# Geoffrey_s_Holiday_Ornament_Design.net
KiCad netlist of a schematic drawn in EAGLE
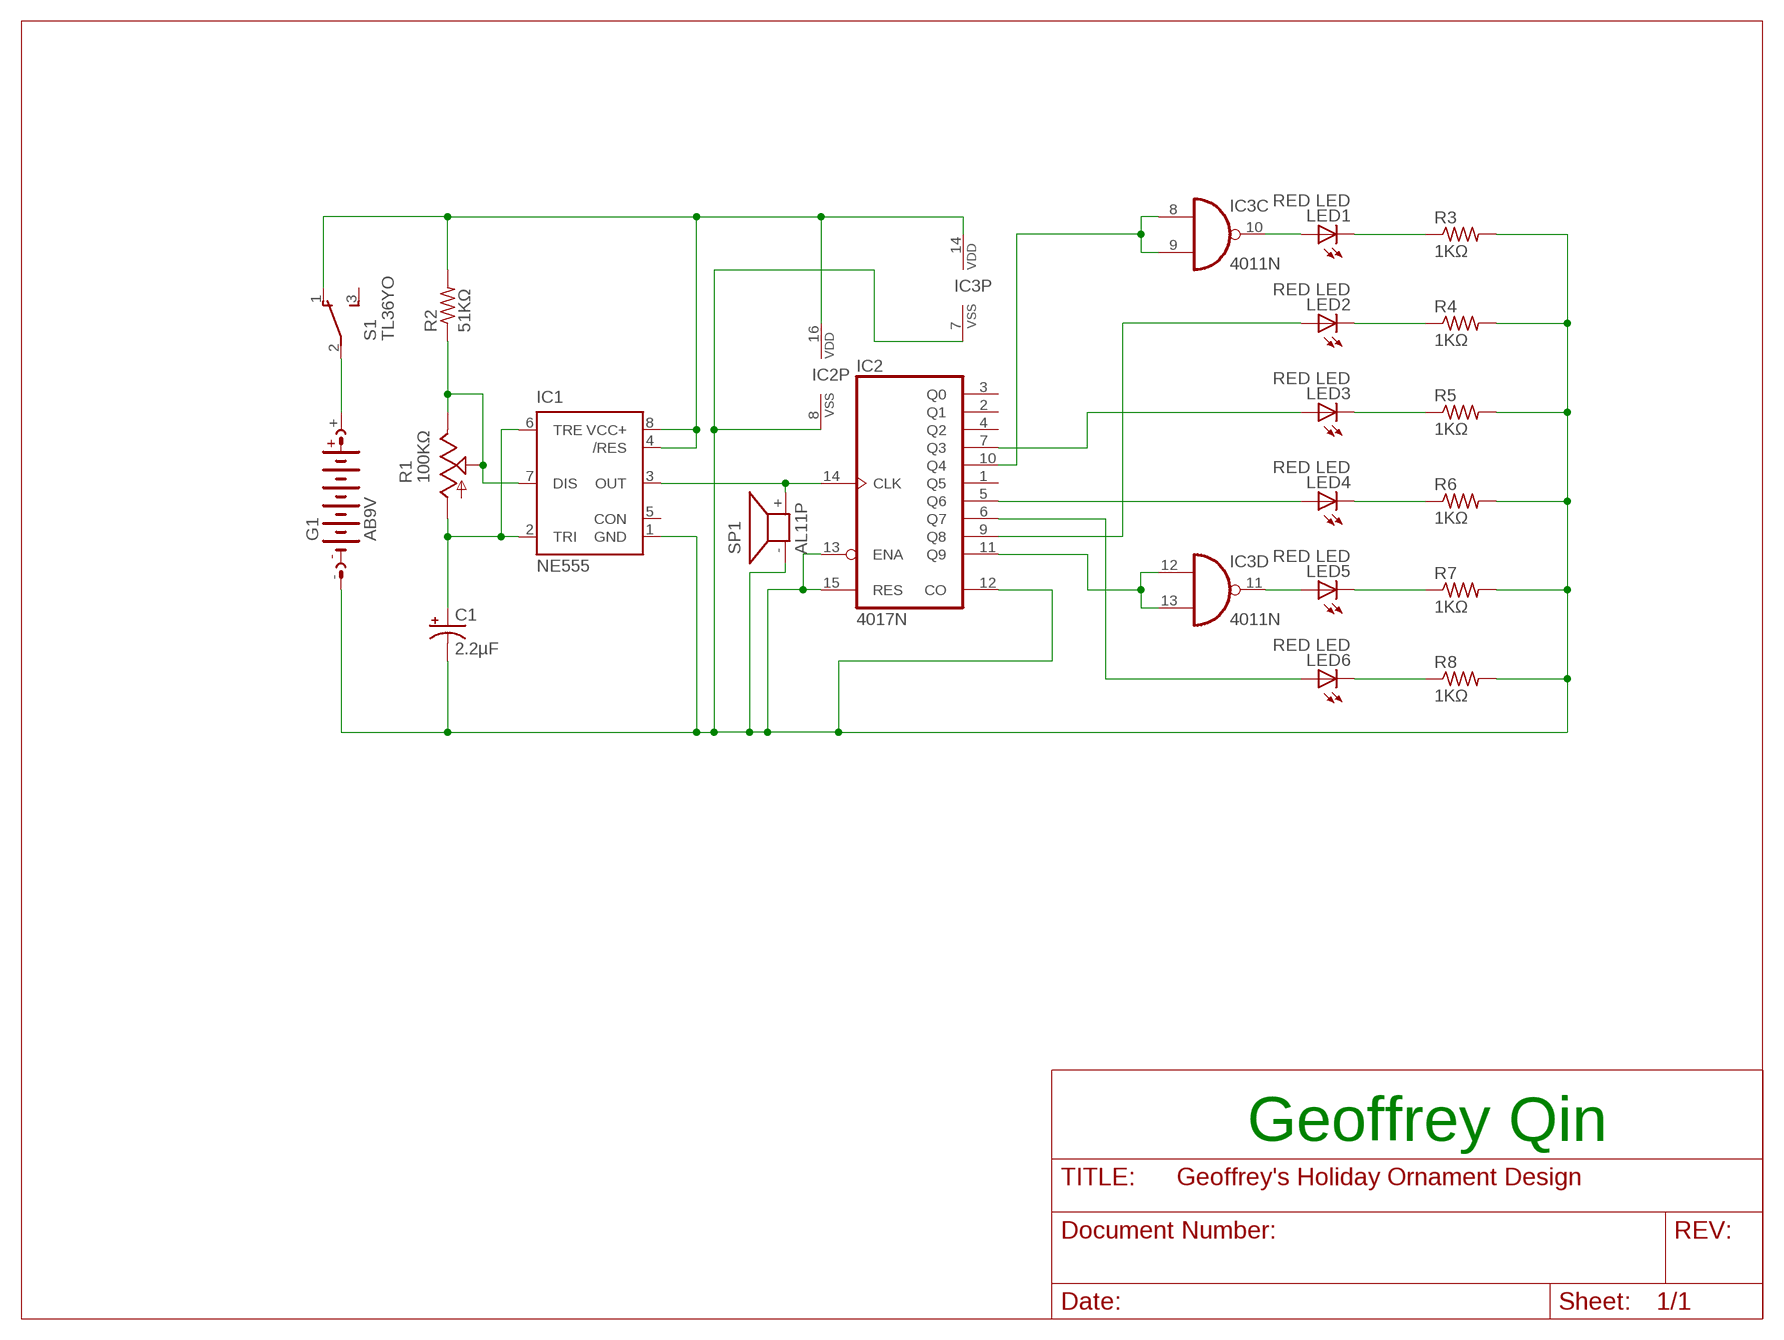
[diagram p0: schematic, sheet 1]

(export (version "E")
  (design (tool "Eeschema 10.0.6"))
  (components
    (comp (ref "C1")
      (value "2.2µF")
      (footprint "eagle-import:E2,5-5")
      (libsource (lib "eagle-import") (part "CPOL-USE2.5-5"))
    )
    (comp (ref "G1")
      (value "AB9V")
      (footprint "eagle-import:AB9V")
      (libsource (lib "eagle-import") (part "AB9V"))
    )
    (comp (ref "IC1")
      (value "NE555")
      (footprint "eagle-import:DIL-08")
      (fields (field (name "MF") "Arrow Electronics") (field (name "MPN") "NE555N"))
      (libsource (lib "eagle-import") (part "NE555"))
    )
    (comp (ref "IC2")
      (value "4017N")
      (footprint "eagle-import:DIL16")
      (libsource (lib "eagle-import") (part "4017N"))
    )
    (comp (ref "IC3")
      (value "4011N")
      (footprint "eagle-import:DIL14")
      (libsource (lib "eagle-import") (part "4011N"))
    )
    (comp (ref "LED1")
      (value "RED LED")
      (footprint "eagle-import:LED5MM")
      (libsource (lib "eagle-import") (part "LED5MM"))
    )
    (comp (ref "LED2")
      (value "RED LED")
      (footprint "eagle-import:LED5MM")
      (libsource (lib "eagle-import") (part "LED5MM"))
    )
    (comp (ref "LED3")
      (value "RED LED")
      (footprint "eagle-import:LED5MM")
      (libsource (lib "eagle-import") (part "LED5MM"))
    )
    (comp (ref "LED4")
      (value "RED LED")
      (footprint "eagle-import:LED5MM")
      (libsource (lib "eagle-import") (part "LED5MM"))
    )
    (comp (ref "LED5")
      (value "RED LED")
      (footprint "eagle-import:LED5MM")
      (libsource (lib "eagle-import") (part "LED5MM"))
    )
    (comp (ref "LED6")
      (value "RED LED")
      (footprint "eagle-import:LED5MM")
      (libsource (lib "eagle-import") (part "LED5MM"))
    )
    (comp (ref "R1")
      (value "100KΩ")
      (footprint "eagle-import:CA9V")
      (libsource (lib "eagle-import") (part "TRIM_US-CA9V"))
    )
    (comp (ref "R2")
      (value "51KΩ")
      (footprint "eagle-import:0207_10")
      (libsource (lib "eagle-import") (part "R-US_0207/10"))
    )
    (comp (ref "R3")
      (value "1KΩ")
      (footprint "eagle-import:0207_10")
      (libsource (lib "eagle-import") (part "R-US_0207/10"))
    )
    (comp (ref "R4")
      (value "1KΩ")
      (footprint "eagle-import:0207_10")
      (libsource (lib "eagle-import") (part "R-US_0207/10"))
    )
    (comp (ref "R5")
      (value "1KΩ")
      (footprint "eagle-import:0207_10")
      (libsource (lib "eagle-import") (part "R-US_0207/10"))
    )
    (comp (ref "R6")
      (value "1KΩ")
      (footprint "eagle-import:0207_10")
      (libsource (lib "eagle-import") (part "R-US_0207/10"))
    )
    (comp (ref "R7")
      (value "1KΩ")
      (footprint "eagle-import:0207_10")
      (libsource (lib "eagle-import") (part "R-US_0207/10"))
    )
    (comp (ref "R8")
      (value "1KΩ")
      (footprint "eagle-import:0207_10")
      (libsource (lib "eagle-import") (part "R-US_0207/10"))
    )
    (comp (ref "S1")
      (value "TL36YO")
      (footprint "eagle-import:TL3XYO")
      (libsource (lib "eagle-import") (part "TL36YO"))
    )
    (comp (ref "SP1")
      (value "AL11P")
      (footprint "eagle-import:AL11P")
      (libsource (lib "eagle-import") (part "AL11P"))
    )
  )
  (nets
    (net (code "1") (name "Net-(IC1-DIS)") (class "Default")
      (node (ref "IC1") (pin "7") (pinfunction "DIS_7") (pintype "input"))
      (node (ref "R1") (pin "E") (pinfunction "E_E") (pintype "passive"))
      (node (ref "R1") (pin "S") (pinfunction "S_S") (pintype "passive"))
      (node (ref "R2") (pin "1") (pinfunction "1_1") (pintype "passive"))
    )
    (net (code "2") (name "Net-(IC1-GND)") (class "Default")
      (node (ref "C1") (pin "-") (pinfunction "-_-") (pintype "passive"))
      (node (ref "G1") (pin "-") (pinfunction "-_-") (pintype "passive"))
      (node (ref "IC1") (pin "1") (pinfunction "GND_1") (pintype "power_in"))
      (node (ref "IC2") (pin "12") (pinfunction "CO_12") (pintype "output"))
      (node (ref "IC2") (pin "13") (pinfunction "ENA_13") (pintype "input"))
      (node (ref "IC2") (pin "15") (pinfunction "RES_15") (pintype "input"))
      (node (ref "IC2") (pin "8") (pinfunction "VSS_8") (pintype "power_in"))
      (node (ref "IC3") (pin "7") (pinfunction "VSS_7") (pintype "power_in"))
      (node (ref "R3") (pin "2") (pinfunction "2_2") (pintype "passive"))
      (node (ref "R4") (pin "2") (pinfunction "2_2") (pintype "passive"))
      (node (ref "R5") (pin "2") (pinfunction "2_2") (pintype "passive"))
      (node (ref "R6") (pin "2") (pinfunction "2_2") (pintype "passive"))
      (node (ref "R7") (pin "2") (pinfunction "2_2") (pintype "passive"))
      (node (ref "R8") (pin "2") (pinfunction "2_2") (pintype "passive"))
      (node (ref "SP1") (pin "-") (pinfunction "1_-") (pintype "passive"))
    )
    (net (code "3") (name "Net-(IC1-OUT)") (class "Default")
      (node (ref "IC1") (pin "3") (pinfunction "OUT_3") (pintype "output"))
      (node (ref "IC2") (pin "14") (pinfunction "CLK_14") (pintype "input"))
      (node (ref "SP1") (pin "+") (pinfunction "2_+") (pintype "passive"))
    )
    (net (code "4") (name "Net-(IC1-TRE)") (class "Default")
      (node (ref "C1") (pin "+") (pinfunction "+_+") (pintype "passive"))
      (node (ref "IC1") (pin "2") (pinfunction "TRI_2") (pintype "input"))
      (node (ref "IC1") (pin "6") (pinfunction "TRE_6") (pintype "input"))
      (node (ref "R1") (pin "A") (pinfunction "A_A") (pintype "passive"))
    )
    (net (code "5") (name "Net-(IC1-VCC+)") (class "Default")
      (node (ref "IC1") (pin "4") (pinfunction "/RES_4") (pintype "input"))
      (node (ref "IC1") (pin "8") (pinfunction "VCC+_8") (pintype "power_in"))
      (node (ref "IC2") (pin "16") (pinfunction "VDD_16") (pintype "power_in"))
      (node (ref "IC3") (pin "14") (pinfunction "VDD_14") (pintype "power_in"))
      (node (ref "R2") (pin "2") (pinfunction "2_2") (pintype "passive"))
      (node (ref "S1") (pin "1") (pinfunction "O_1") (pintype "passive"))
    )
    (net (code "6") (name "Net-(IC2A-Q3)") (class "Default")
      (node (ref "IC2") (pin "7") (pinfunction "Q3_7") (pintype "output"))
      (node (ref "LED3") (pin "A") (pinfunction "A_A") (pintype "passive"))
    )
    (net (code "7") (name "Net-(IC2A-Q4)") (class "Default")
      (node (ref "IC2") (pin "10") (pinfunction "Q4_10") (pintype "output"))
      (node (ref "IC3") (pin "8") (pinfunction "I0_8") (pintype "input"))
      (node (ref "IC3") (pin "9") (pinfunction "I1_9") (pintype "input"))
    )
    (net (code "8") (name "Net-(IC2A-Q6)") (class "Default")
      (node (ref "IC2") (pin "5") (pinfunction "Q6_5") (pintype "output"))
      (node (ref "LED4") (pin "A") (pinfunction "A_A") (pintype "passive"))
    )
    (net (code "9") (name "Net-(IC2A-Q7)") (class "Default")
      (node (ref "IC2") (pin "6") (pinfunction "Q7_6") (pintype "output"))
      (node (ref "LED6") (pin "A") (pinfunction "A_A") (pintype "passive"))
    )
    (net (code "10") (name "Net-(IC2A-Q8)") (class "Default")
      (node (ref "IC2") (pin "9") (pinfunction "Q8_9") (pintype "output"))
      (node (ref "LED2") (pin "A") (pinfunction "A_A") (pintype "passive"))
    )
    (net (code "11") (name "Net-(IC2A-Q9)") (class "Default")
      (node (ref "IC2") (pin "11") (pinfunction "Q9_11") (pintype "output"))
      (node (ref "IC3") (pin "12") (pinfunction "I0_12") (pintype "input"))
      (node (ref "IC3") (pin "13") (pinfunction "I1_13") (pintype "input"))
    )
    (net (code "12") (name "Net-(IC3C-O)") (class "Default")
      (node (ref "IC3") (pin "10") (pinfunction "O_10") (pintype "output"))
      (node (ref "LED1") (pin "A") (pinfunction "A_A") (pintype "passive"))
    )
    (net (code "13") (name "Net-(IC3D-O)") (class "Default")
      (node (ref "IC3") (pin "11") (pinfunction "O_11") (pintype "output"))
      (node (ref "LED5") (pin "A") (pinfunction "A_A") (pintype "passive"))
    )
    (net (code "14") (name "Net-(LED1-C)") (class "Default")
      (node (ref "LED1") (pin "K") (pinfunction "C_K") (pintype "passive"))
      (node (ref "R3") (pin "1") (pinfunction "1_1") (pintype "passive"))
    )
    (net (code "15") (name "Net-(LED2-C)") (class "Default")
      (node (ref "LED2") (pin "K") (pinfunction "C_K") (pintype "passive"))
      (node (ref "R4") (pin "1") (pinfunction "1_1") (pintype "passive"))
    )
    (net (code "16") (name "Net-(LED3-C)") (class "Default")
      (node (ref "LED3") (pin "K") (pinfunction "C_K") (pintype "passive"))
      (node (ref "R5") (pin "1") (pinfunction "1_1") (pintype "passive"))
    )
    (net (code "17") (name "Net-(LED4-C)") (class "Default")
      (node (ref "LED4") (pin "K") (pinfunction "C_K") (pintype "passive"))
      (node (ref "R6") (pin "1") (pinfunction "1_1") (pintype "passive"))
    )
    (net (code "18") (name "Net-(LED5-C)") (class "Default")
      (node (ref "LED5") (pin "K") (pinfunction "C_K") (pintype "passive"))
      (node (ref "R7") (pin "1") (pinfunction "1_1") (pintype "passive"))
    )
    (net (code "19") (name "Net-(LED6-C)") (class "Default")
      (node (ref "LED6") (pin "K") (pinfunction "C_K") (pintype "passive"))
      (node (ref "R8") (pin "1") (pinfunction "1_1") (pintype "passive"))
    )
    (net (code "20") (name "Net-(S1-P)") (class "Default")
      (node (ref "G1") (pin "+") (pinfunction "+_+") (pintype "passive"))
      (node (ref "S1") (pin "2") (pinfunction "P_2") (pintype "passive"))
    )
    (net (code "21") (name "unconnected-(IC1-CON-Pad5)") (class "Default")
      (node (ref "IC1") (pin "5") (pinfunction "CON_5") (pintype "input"))
    )
    (net (code "22") (name "unconnected-(IC2A-Q0-Pad3)") (class "Default")
      (node (ref "IC2") (pin "3") (pinfunction "Q0_3") (pintype "output"))
    )
    (net (code "23") (name "unconnected-(IC2A-Q1-Pad2)") (class "Default")
      (node (ref "IC2") (pin "2") (pinfunction "Q1_2") (pintype "output"))
    )
    (net (code "24") (name "unconnected-(IC2A-Q2-Pad4)") (class "Default")
      (node (ref "IC2") (pin "4") (pinfunction "Q2_4") (pintype "output"))
    )
    (net (code "25") (name "unconnected-(IC2A-Q5-Pad1)") (class "Default")
      (node (ref "IC2") (pin "1") (pinfunction "Q5_1") (pintype "output"))
    )
    (net (code "26") (name "unconnected-(S1-S-Pad3)") (class "Default")
      (node (ref "S1") (pin "3") (pinfunction "S_3") (pintype "passive"))
    )
  )
)
